# autopilot.net
KiCad netlist of a schematic drawn in EAGLE
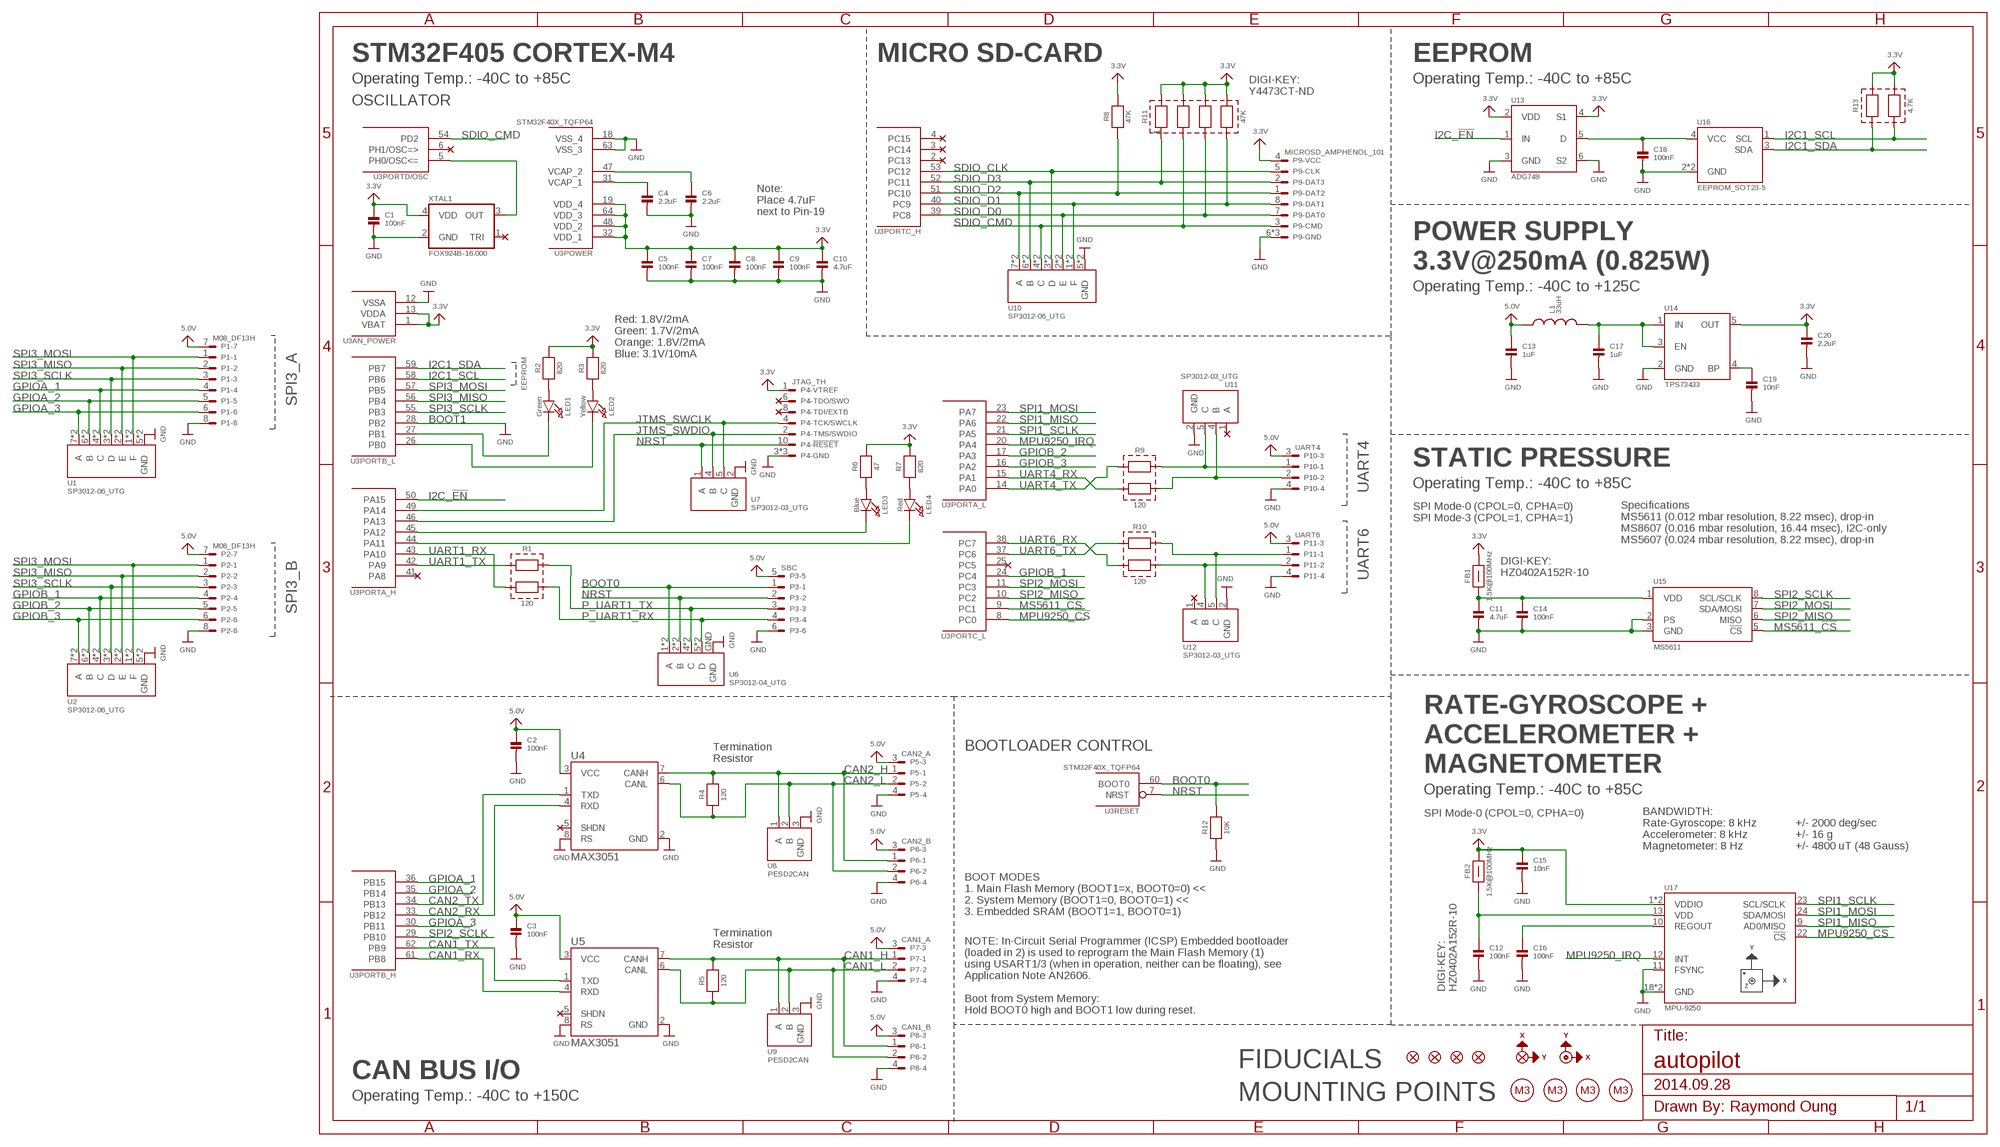
[diagram p0: schematic, sheet 1]

(export (version "E")
  (design (tool "Eeschema 10.0.6"))
  (components
    (comp (ref "AXIS3D1")
      (value "AXIS3D_DOWN")
      (footprint "eagle-import:AXIS3D_DOWN")
      (libsource (lib "eagle-import") (part "AXIS3D_DOWN"))
    )
    (comp (ref "AXIS3D2")
      (value "AXIS3D_UP")
      (footprint "eagle-import:AXIS3D_UP")
      (libsource (lib "eagle-import") (part "AXIS3D_UP"))
    )
    (comp (ref "C1")
      (value "100nF")
      (footprint "eagle-import:0402")
      (libsource (lib "eagle-import") (part "CAP_CERAMIC0402"))
    )
    (comp (ref "C2")
      (value "100nF")
      (footprint "eagle-import:0402")
      (libsource (lib "eagle-import") (part "CAP_CERAMIC0402"))
    )
    (comp (ref "C3")
      (value "100nF")
      (footprint "eagle-import:0402")
      (libsource (lib "eagle-import") (part "CAP_CERAMIC0402"))
    )
    (comp (ref "C4")
      (value "2.2uF")
      (footprint "eagle-import:0402")
      (libsource (lib "eagle-import") (part "CAP_CERAMIC0402"))
    )
    (comp (ref "C5")
      (value "100nF")
      (footprint "eagle-import:0402")
      (libsource (lib "eagle-import") (part "CAP_CERAMIC0402"))
    )
    (comp (ref "C6")
      (value "2.2uF")
      (footprint "eagle-import:0402")
      (libsource (lib "eagle-import") (part "CAP_CERAMIC0402"))
    )
    (comp (ref "C7")
      (value "100nF")
      (footprint "eagle-import:0402")
      (libsource (lib "eagle-import") (part "CAP_CERAMIC0402"))
    )
    (comp (ref "C8")
      (value "100nF")
      (footprint "eagle-import:0402")
      (libsource (lib "eagle-import") (part "CAP_CERAMIC0402"))
    )
    (comp (ref "C9")
      (value "100nF")
      (footprint "eagle-import:0402")
      (libsource (lib "eagle-import") (part "CAP_CERAMIC0402"))
    )
    (comp (ref "C10")
      (value "4.7uF")
      (footprint "eagle-import:0402")
      (libsource (lib "eagle-import") (part "CAP_CERAMIC0402"))
    )
    (comp (ref "C11")
      (value "4.7uF")
      (footprint "eagle-import:0402")
      (libsource (lib "eagle-import") (part "CAP_CERAMIC0402"))
    )
    (comp (ref "C12")
      (value "100nF")
      (footprint "eagle-import:0402")
      (libsource (lib "eagle-import") (part "CAP_CERAMIC0402"))
    )
    (comp (ref "C13")
      (value "1uF")
      (footprint "eagle-import:0402")
      (libsource (lib "eagle-import") (part "CAP_CERAMIC0402"))
    )
    (comp (ref "C14")
      (value "100nF")
      (footprint "eagle-import:0402")
      (libsource (lib "eagle-import") (part "CAP_CERAMIC0402"))
    )
    (comp (ref "C15")
      (value "10nF")
      (footprint "eagle-import:0402")
      (libsource (lib "eagle-import") (part "CAP_CERAMIC0402"))
    )
    (comp (ref "C16")
      (value "100nF")
      (footprint "eagle-import:0402")
      (libsource (lib "eagle-import") (part "CAP_CERAMIC0402"))
    )
    (comp (ref "C17")
      (value "1uF")
      (footprint "eagle-import:0402")
      (libsource (lib "eagle-import") (part "CAP_CERAMIC0402"))
    )
    (comp (ref "C18")
      (value "100nF")
      (footprint "eagle-import:0402")
      (libsource (lib "eagle-import") (part "CAP_CERAMIC0402"))
    )
    (comp (ref "C19")
      (value "10nF")
      (footprint "eagle-import:0402")
      (libsource (lib "eagle-import") (part "CAP_CERAMIC0402"))
    )
    (comp (ref "C20")
      (value "2.2uF")
      (footprint "eagle-import:0402")
      (libsource (lib "eagle-import") (part "CAP_CERAMIC0402"))
    )
    (comp (ref "FB1")
      (value "1.5K@100MHz")
      (footprint "eagle-import:0402")
      (libsource (lib "eagle-import") (part "FERRITE_0402"))
    )
    (comp (ref "FB2")
      (value "1.5K@100MHz")
      (footprint "eagle-import:0402")
      (libsource (lib "eagle-import") (part "FERRITE_0402"))
    )
    (comp (ref "L1")
      (value "33uH")
      (footprint "eagle-import:1210")
      (libsource (lib "eagle-import") (part "INDUCTOR_1210"))
    )
    (comp (ref "LED1")
      (value "Green")
      (footprint "eagle-import:CHIPLED_0603")
      (libsource (lib "eagle-import") (part "LED_0603"))
    )
    (comp (ref "LED2")
      (value "Yellow")
      (footprint "eagle-import:CHIPLED_0603")
      (libsource (lib "eagle-import") (part "LED_0603"))
    )
    (comp (ref "LED3")
      (value "Blue")
      (footprint "eagle-import:CHIPLED_0603")
      (libsource (lib "eagle-import") (part "LED_0603"))
    )
    (comp (ref "LED4")
      (value "Red")
      (footprint "eagle-import:CHIPLED_0603")
      (libsource (lib "eagle-import") (part "LED_0603"))
    )
    (comp (ref "MP1")
      (value "M3")
      (footprint "eagle-import:MP_M3")
      (libsource (lib "eagle-import") (part "M3"))
    )
    (comp (ref "MP2")
      (value "M3")
      (footprint "eagle-import:MP_M3")
      (libsource (lib "eagle-import") (part "M3"))
    )
    (comp (ref "MP3")
      (value "M3")
      (footprint "eagle-import:MP_M3")
      (libsource (lib "eagle-import") (part "M3"))
    )
    (comp (ref "MP4")
      (value "M3")
      (footprint "eagle-import:MP_M3")
      (libsource (lib "eagle-import") (part "M3"))
    )
    (comp (ref "P1")
      (value "M08_DF13H")
      (footprint "eagle-import:DF13A-8P-1.25H")
      (libsource (lib "eagle-import") (part "M08_DF13H"))
    )
    (comp (ref "P2")
      (value "M08_DF13H")
      (footprint "eagle-import:DF13A-8P-1.25H")
      (libsource (lib "eagle-import") (part "M08_DF13H"))
    )
    (comp (ref "P3")
      (value "SBC")
      (footprint "eagle-import:DF13A-6P-1.25H")
      (libsource (lib "eagle-import") (part "M06_DF13H"))
    )
    (comp (ref "P4")
      (value "JTAG_TH")
      (footprint "eagle-import:FTSH-105-01-XXX-DV")
      (libsource (lib "eagle-import") (part "JTAG_TH"))
    )
    (comp (ref "P5")
      (value "CAN2_A")
      (footprint "eagle-import:DF13A-4P-1.25H")
      (libsource (lib "eagle-import") (part "M04_DF13H"))
    )
    (comp (ref "P6")
      (value "CAN2_B")
      (footprint "eagle-import:DF13A-4P-1.25H")
      (libsource (lib "eagle-import") (part "M04_DF13H"))
    )
    (comp (ref "P7")
      (value "CAN1_A")
      (footprint "eagle-import:DF13A-4P-1.25H")
      (libsource (lib "eagle-import") (part "M04_DF13H"))
    )
    (comp (ref "P8")
      (value "CAN1_B")
      (footprint "eagle-import:DF13A-4P-1.25H")
      (libsource (lib "eagle-import") (part "M04_DF13H"))
    )
    (comp (ref "P9")
      (value "MICROSD_AMPHENOL_101")
      (footprint "eagle-import:AMPHENOL_101-00660-68")
      (libsource (lib "eagle-import") (part "MICROSD_AMPHENOL_101"))
    )
    (comp (ref "P10")
      (value "UART4")
      (footprint "eagle-import:DF13A-4P-1.25H")
      (libsource (lib "eagle-import") (part "M04_DF13H"))
    )
    (comp (ref "P11")
      (value "UART6")
      (footprint "eagle-import:DF13A-4P-1.25H")
      (libsource (lib "eagle-import") (part "M04_DF13H"))
    )
    (comp (ref "R1")
      (value "120")
      (footprint "eagle-import:EXBV4V")
      (libsource (lib "eagle-import") (part "RESISTOR2_0603X2"))
    )
    (comp (ref "R2")
      (value "820")
      (footprint "eagle-import:0402")
      (libsource (lib "eagle-import") (part "RESISTOR0402"))
    )
    (comp (ref "R3")
      (value "820")
      (footprint "eagle-import:0402")
      (libsource (lib "eagle-import") (part "RESISTOR0402"))
    )
    (comp (ref "R4")
      (value "120")
      (footprint "eagle-import:0603")
      (libsource (lib "eagle-import") (part "RESISTOR0603"))
    )
    (comp (ref "R5")
      (value "120")
      (footprint "eagle-import:0603")
      (libsource (lib "eagle-import") (part "RESISTOR0603"))
    )
    (comp (ref "R6")
      (value "47")
      (footprint "eagle-import:0402")
      (libsource (lib "eagle-import") (part "RESISTOR0402"))
    )
    (comp (ref "R7")
      (value "820")
      (footprint "eagle-import:0402")
      (libsource (lib "eagle-import") (part "RESISTOR0402"))
    )
    (comp (ref "R8")
      (value "47K")
      (footprint "eagle-import:0603")
      (libsource (lib "eagle-import") (part "RESISTOR0603"))
    )
    (comp (ref "R9")
      (value "120")
      (footprint "eagle-import:EXBV4V")
      (libsource (lib "eagle-import") (part "RESISTOR2_0603X2"))
    )
    (comp (ref "R10")
      (value "120")
      (footprint "eagle-import:EXBV4V")
      (libsource (lib "eagle-import") (part "RESISTOR2_0603X2"))
    )
    (comp (ref "R11")
      (value "47K")
      (footprint "eagle-import:EXBV8V")
      (libsource (lib "eagle-import") (part "RESISTOR4_0603X4"))
    )
    (comp (ref "R12")
      (value "10K")
      (footprint "eagle-import:0402")
      (libsource (lib "eagle-import") (part "RESISTOR0402"))
    )
    (comp (ref "R13")
      (value "4.7K")
      (footprint "eagle-import:EXBV4V")
      (libsource (lib "eagle-import") (part "RESISTOR2_0603X2"))
    )
    (comp (ref "REF1")
      (value "FIDUCIAL1X2.5")
      (footprint "eagle-import:POINT-1MM")
      (libsource (lib "eagle-import") (part "FIDUCIAL1X2.5"))
    )
    (comp (ref "REF2")
      (value "FIDUCIAL1X2.5")
      (footprint "eagle-import:POINT-1MM")
      (libsource (lib "eagle-import") (part "FIDUCIAL1X2.5"))
    )
    (comp (ref "REF3")
      (value "FIDUCIAL1X2.5")
      (footprint "eagle-import:POINT-1MM")
      (libsource (lib "eagle-import") (part "FIDUCIAL1X2.5"))
    )
    (comp (ref "REF4")
      (value "FIDUCIAL1X2.5")
      (footprint "eagle-import:POINT-1MM")
      (libsource (lib "eagle-import") (part "FIDUCIAL1X2.5"))
    )
    (comp (ref "U1")
      (value "SP3012-06_UTG")
      (footprint "eagle-import:UDFN14")
      (libsource (lib "eagle-import") (part "SP3012-06_UTG"))
    )
    (comp (ref "U2")
      (value "SP3012-06_UTG")
      (footprint "eagle-import:UDFN14")
      (libsource (lib "eagle-import") (part "SP3012-06_UTG"))
    )
    (comp (ref "U3")
      (value "STM32F40X_TQFP64")
      (footprint "eagle-import:TQFP64")
      (libsource (lib "eagle-import") (part "STM32F40X_TQFP64"))
    )
    (comp (ref "U4")
      (value "MAX3051")
      (footprint "eagle-import:SOT23-8")
      (libsource (lib "eagle-import") (part "MAX3051"))
    )
    (comp (ref "U5")
      (value "MAX3051")
      (footprint "eagle-import:SOT23-8")
      (libsource (lib "eagle-import") (part "MAX3051"))
    )
    (comp (ref "U6")
      (value "SP3012-04_UTG")
      (footprint "eagle-import:UDFN10")
      (libsource (lib "eagle-import") (part "SP3012-04_UTG"))
    )
    (comp (ref "U7")
      (value "SP3012-03_UTG")
      (footprint "eagle-import:UDFN06")
      (libsource (lib "eagle-import") (part "SP3012-03_UTG"))
    )
    (comp (ref "U8")
      (value "PESD2CAN")
      (footprint "eagle-import:SOT23-3")
      (libsource (lib "eagle-import") (part "PESD2CAN"))
    )
    (comp (ref "U9")
      (value "PESD2CAN")
      (footprint "eagle-import:SOT23-3")
      (libsource (lib "eagle-import") (part "PESD2CAN"))
    )
    (comp (ref "U10")
      (value "SP3012-06_UTG")
      (footprint "eagle-import:UDFN14")
      (libsource (lib "eagle-import") (part "SP3012-06_UTG"))
    )
    (comp (ref "U11")
      (value "SP3012-03_UTG")
      (footprint "eagle-import:UDFN06")
      (libsource (lib "eagle-import") (part "SP3012-03_UTG"))
    )
    (comp (ref "U12")
      (value "SP3012-03_UTG")
      (footprint "eagle-import:UDFN06")
      (libsource (lib "eagle-import") (part "SP3012-03_UTG"))
    )
    (comp (ref "U13")
      (value "ADG749")
      (footprint "eagle-import:SOT-363")
      (libsource (lib "eagle-import") (part "ADG749"))
    )
    (comp (ref "U14")
      (value "TPS73433")
      (footprint "eagle-import:SOT23-5")
      (libsource (lib "eagle-import") (part "TPS73433"))
    )
    (comp (ref "U15")
      (value "MS5611")
      (footprint "eagle-import:MS5611")
      (libsource (lib "eagle-import") (part "MS5611"))
    )
    (comp (ref "U16")
      (value "EEPROM_SOT23-5")
      (footprint "eagle-import:SOT23-5")
      (libsource (lib "eagle-import") (part "EEPROM_SOT23-5"))
    )
    (comp (ref "U17")
      (value "MPU-9250")
      (footprint "eagle-import:MPU-3X3")
      (libsource (lib "eagle-import") (part "MPU-9250"))
    )
    (comp (ref "XTAL1")
      (value "FOX924B-16.000")
      (footprint "eagle-import:OSCILLATOR-5.0X3.2A")
      (libsource (lib "eagle-import") (part "TCXO_5.0X3.2A"))
    )
  )
  (nets
    (net (code "1") (name "/BOOT0") (class "Default")
      (node (ref "P3") (pin "1") (pinfunction "S_1") (pintype "passive"))
      (node (ref "R12") (pin "2") (pinfunction "2_2") (pintype "passive"))
      (node (ref "U3") (pin "60") (pinfunction "BOOT0_60") (pintype "input"))
      (node (ref "U6") (pin "1") (pinfunction "A_1") (pintype "bidirectional"))
      (node (ref "U6") (pin "10") (pinfunction "A_10") (pintype "bidirectional"))
    )
    (net (code "2") (name "/CAN1_H") (class "Default")
      (node (ref "P7") (pin "1") (pinfunction "S_1") (pintype "passive"))
      (node (ref "P8") (pin "1") (pinfunction "S_1") (pintype "passive"))
      (node (ref "R5") (pin "2") (pinfunction "2_2") (pintype "passive"))
      (node (ref "U5") (pin "7") (pinfunction "CANH_7") (pintype "bidirectional"))
      (node (ref "U9") (pin "1") (pinfunction "A_1") (pintype "bidirectional"))
    )
    (net (code "3") (name "/CAN1_L") (class "Default")
      (node (ref "P7") (pin "2") (pinfunction "S_2") (pintype "passive"))
      (node (ref "P8") (pin "2") (pinfunction "S_2") (pintype "passive"))
      (node (ref "R5") (pin "1") (pinfunction "1_1") (pintype "passive"))
      (node (ref "U5") (pin "6") (pinfunction "CANL_6") (pintype "bidirectional"))
      (node (ref "U9") (pin "2") (pinfunction "B_2") (pintype "bidirectional"))
    )
    (net (code "4") (name "/CAN1_RX") (class "Default")
      (node (ref "U3") (pin "61") (pinfunction "PB8_61") (pintype "bidirectional"))
      (node (ref "U5") (pin "4") (pinfunction "RXD_4") (pintype "bidirectional"))
    )
    (net (code "5") (name "/CAN1_TX") (class "Default")
      (node (ref "U3") (pin "62") (pinfunction "PB9_62") (pintype "bidirectional"))
      (node (ref "U5") (pin "1") (pinfunction "TXD_1") (pintype "bidirectional"))
    )
    (net (code "6") (name "/CAN2_H") (class "Default")
      (node (ref "P5") (pin "1") (pinfunction "S_1") (pintype "passive"))
      (node (ref "P6") (pin "1") (pinfunction "S_1") (pintype "passive"))
      (node (ref "R4") (pin "2") (pinfunction "2_2") (pintype "passive"))
      (node (ref "U4") (pin "7") (pinfunction "CANH_7") (pintype "bidirectional"))
      (node (ref "U8") (pin "1") (pinfunction "A_1") (pintype "bidirectional"))
    )
    (net (code "7") (name "/CAN2_L") (class "Default")
      (node (ref "P5") (pin "2") (pinfunction "S_2") (pintype "passive"))
      (node (ref "P6") (pin "2") (pinfunction "S_2") (pintype "passive"))
      (node (ref "R4") (pin "1") (pinfunction "1_1") (pintype "passive"))
      (node (ref "U4") (pin "6") (pinfunction "CANL_6") (pintype "bidirectional"))
      (node (ref "U8") (pin "2") (pinfunction "B_2") (pintype "bidirectional"))
    )
    (net (code "8") (name "/CAN2_RX") (class "Default")
      (node (ref "U3") (pin "33") (pinfunction "PB12_33") (pintype "bidirectional"))
      (node (ref "U4") (pin "4") (pinfunction "RXD_4") (pintype "bidirectional"))
    )
    (net (code "9") (name "/CAN2_TX") (class "Default")
      (node (ref "U3") (pin "34") (pinfunction "PB13_34") (pintype "bidirectional"))
      (node (ref "U4") (pin "1") (pinfunction "TXD_1") (pintype "bidirectional"))
    )
    (net (code "10") (name "/GPIOA_1") (class "Default")
      (node (ref "P1") (pin "4") (pinfunction "S_4") (pintype "passive"))
      (node (ref "U1") (pin "11") (pinfunction "C_11") (pintype "passive"))
      (node (ref "U1") (pin "4") (pinfunction "C_4") (pintype "passive"))
      (node (ref "U3") (pin "36") (pinfunction "PB15_36") (pintype "bidirectional"))
    )
    (net (code "11") (name "/GPIOA_2") (class "Default")
      (node (ref "P1") (pin "5") (pinfunction "S_5") (pintype "passive"))
      (node (ref "U1") (pin "6") (pinfunction "B_6") (pintype "passive"))
      (node (ref "U1") (pin "9") (pinfunction "B_9") (pintype "passive"))
      (node (ref "U3") (pin "35") (pinfunction "PB14_35") (pintype "bidirectional"))
    )
    (net (code "12") (name "/GPIOA_3") (class "Default")
      (node (ref "P1") (pin "6") (pinfunction "S_6") (pintype "passive"))
      (node (ref "U1") (pin "7") (pinfunction "A_7") (pintype "passive"))
      (node (ref "U1") (pin "8") (pinfunction "A_8") (pintype "passive"))
      (node (ref "U3") (pin "30") (pinfunction "PB11_30") (pintype "bidirectional"))
    )
    (net (code "13") (name "/GPIOB_1") (class "Default")
      (node (ref "P2") (pin "4") (pinfunction "S_4") (pintype "passive"))
      (node (ref "U2") (pin "11") (pinfunction "C_11") (pintype "passive"))
      (node (ref "U2") (pin "4") (pinfunction "C_4") (pintype "passive"))
      (node (ref "U3") (pin "24") (pinfunction "PC4_24") (pintype "bidirectional"))
    )
    (net (code "14") (name "/GPIOB_2") (class "Default")
      (node (ref "P2") (pin "5") (pinfunction "S_5") (pintype "passive"))
      (node (ref "U2") (pin "6") (pinfunction "B_6") (pintype "passive"))
      (node (ref "U2") (pin "9") (pinfunction "B_9") (pintype "passive"))
      (node (ref "U3") (pin "17") (pinfunction "PA3_17") (pintype "bidirectional"))
    )
    (net (code "15") (name "/GPIOB_3") (class "Default")
      (node (ref "P2") (pin "6") (pinfunction "S_6") (pintype "passive"))
      (node (ref "U2") (pin "7") (pinfunction "A_7") (pintype "passive"))
      (node (ref "U2") (pin "8") (pinfunction "A_8") (pintype "passive"))
      (node (ref "U3") (pin "16") (pinfunction "PA2_16") (pintype "bidirectional"))
    )
    (net (code "16") (name "/I2C1_SCL") (class "Default")
      (node (ref "R13") (pin "2") (pinfunction "2_2") (pintype "passive"))
      (node (ref "U16") (pin "1") (pinfunction "SCL_1") (pintype "bidirectional"))
      (node (ref "U3") (pin "58") (pinfunction "PB6_58") (pintype "bidirectional"))
    )
    (net (code "17") (name "/I2C1_SDA") (class "Default")
      (node (ref "R13") (pin "1") (pinfunction "1_1") (pintype "passive"))
      (node (ref "U16") (pin "3") (pinfunction "SDA_3") (pintype "bidirectional"))
      (node (ref "U3") (pin "59") (pinfunction "PB7_59") (pintype "bidirectional"))
    )
    (net (code "18") (name "/I2C_~{EN}") (class "Default")
      (node (ref "U13") (pin "1") (pinfunction "IN_1") (pintype "bidirectional"))
      (node (ref "U3") (pin "50") (pinfunction "PA15_50") (pintype "bidirectional"))
    )
    (net (code "19") (name "/JTMS_SWCLK") (class "Default")
      (node (ref "P4") (pin "4") (pinfunction "S_4") (pintype "passive"))
      (node (ref "U3") (pin "49") (pinfunction "PA14_49") (pintype "bidirectional"))
      (node (ref "U7") (pin "5") (pinfunction "C_5") (pintype "bidirectional"))
    )
    (net (code "20") (name "/JTMS_SWDIO") (class "Default")
      (node (ref "P4") (pin "2") (pinfunction "S_2") (pintype "passive"))
      (node (ref "U3") (pin "46") (pinfunction "PA13_46") (pintype "bidirectional"))
      (node (ref "U7") (pin "4") (pinfunction "B_4") (pintype "bidirectional"))
    )
    (net (code "21") (name "/MPU9250_IRQ") (class "Default")
      (node (ref "U17") (pin "12") (pinfunction "INT_12") (pintype "bidirectional"))
      (node (ref "U3") (pin "20") (pinfunction "PA4_20") (pintype "bidirectional"))
    )
    (net (code "22") (name "/MPU9250_~{CS}") (class "Default")
      (node (ref "U17") (pin "22") (pinfunction "~{CS}_22") (pintype "bidirectional"))
      (node (ref "U3") (pin "8") (pinfunction "PC0_8") (pintype "bidirectional"))
    )
    (net (code "23") (name "/MS5611_~{CS}") (class "Default")
      (node (ref "U15") (pin "5") (pinfunction "~{CS}_5") (pintype "bidirectional"))
      (node (ref "U3") (pin "9") (pinfunction "PC1_9") (pintype "bidirectional"))
    )
    (net (code "24") (name "/NRST") (class "Default")
      (node (ref "P3") (pin "2") (pinfunction "S_2") (pintype "passive"))
      (node (ref "P4") (pin "10") (pinfunction "S_10") (pintype "passive"))
      (node (ref "U3") (pin "7") (pinfunction "NRST_7") (pintype "input"))
      (node (ref "U6") (pin "2") (pinfunction "B_2") (pintype "bidirectional"))
      (node (ref "U6") (pin "9") (pinfunction "B_9") (pintype "bidirectional"))
      (node (ref "U7") (pin "1") (pinfunction "A_1") (pintype "bidirectional"))
    )
    (net (code "25") (name "/P_UART1_RX") (class "Default")
      (node (ref "P3") (pin "4") (pinfunction "S_4") (pintype "passive"))
      (node (ref "R1") (pin "3") (pinfunction "3_3") (pintype "passive"))
      (node (ref "U6") (pin "5") (pinfunction "D_5") (pintype "bidirectional"))
      (node (ref "U6") (pin "6") (pinfunction "D_6") (pintype "bidirectional"))
    )
    (net (code "26") (name "/P_UART1_TX") (class "Default")
      (node (ref "P3") (pin "3") (pinfunction "S_3") (pintype "passive"))
      (node (ref "R1") (pin "4") (pinfunction "4_4") (pintype "passive"))
      (node (ref "U6") (pin "4") (pinfunction "C_4") (pintype "bidirectional"))
      (node (ref "U6") (pin "7") (pinfunction "C_7") (pintype "bidirectional"))
    )
    (net (code "27") (name "/SDIO_CLK") (class "Default")
      (node (ref "P9") (pin "5") (pinfunction "S_5") (pintype "passive"))
      (node (ref "U10") (pin "12") (pinfunction "D_12") (pintype "passive"))
      (node (ref "U10") (pin "3") (pinfunction "D_3") (pintype "passive"))
      (node (ref "U3") (pin "53") (pinfunction "PC12_53") (pintype "bidirectional"))
    )
    (net (code "28") (name "/SDIO_CMD") (class "Default")
      (node (ref "P9") (pin "3") (pinfunction "S_3") (pintype "passive"))
      (node (ref "R11") (pin "2") (pinfunction "2_2") (pintype "passive"))
      (node (ref "U10") (pin "11") (pinfunction "C_11") (pintype "passive"))
      (node (ref "U10") (pin "4") (pinfunction "C_4") (pintype "passive"))
      (node (ref "U3") (pin "54") (pinfunction "PD2_54") (pintype "bidirectional"))
    )
    (net (code "29") (name "/SDIO_D0") (class "Default")
      (node (ref "P9") (pin "7") (pinfunction "S_7") (pintype "passive"))
      (node (ref "R11") (pin "3") (pinfunction "3_3") (pintype "passive"))
      (node (ref "U10") (pin "13") (pinfunction "E_13") (pintype "passive"))
      (node (ref "U10") (pin "2") (pinfunction "E_2") (pintype "passive"))
      (node (ref "U3") (pin "39") (pinfunction "PC8_39") (pintype "bidirectional"))
    )
    (net (code "30") (name "/SDIO_D1") (class "Default")
      (node (ref "P9") (pin "8") (pinfunction "S_8") (pintype "passive"))
      (node (ref "R11") (pin "4") (pinfunction "4_4") (pintype "passive"))
      (node (ref "U10") (pin "1") (pinfunction "F_1") (pintype "passive"))
      (node (ref "U10") (pin "14") (pinfunction "F_14") (pintype "passive"))
      (node (ref "U3") (pin "40") (pinfunction "PC9_40") (pintype "bidirectional"))
    )
    (net (code "31") (name "/SDIO_D2") (class "Default")
      (node (ref "P9") (pin "1") (pinfunction "S_1") (pintype "passive"))
      (node (ref "R8") (pin "1") (pinfunction "1_1") (pintype "passive"))
      (node (ref "U10") (pin "7") (pinfunction "A_7") (pintype "passive"))
      (node (ref "U10") (pin "8") (pinfunction "A_8") (pintype "passive"))
      (node (ref "U3") (pin "51") (pinfunction "PC10_51") (pintype "bidirectional"))
    )
    (net (code "32") (name "/SDIO_D3") (class "Default")
      (node (ref "P9") (pin "2") (pinfunction "S_2") (pintype "passive"))
      (node (ref "R11") (pin "1") (pinfunction "1_1") (pintype "passive"))
      (node (ref "U10") (pin "6") (pinfunction "B_6") (pintype "passive"))
      (node (ref "U10") (pin "9") (pinfunction "B_9") (pintype "passive"))
      (node (ref "U3") (pin "52") (pinfunction "PC11_52") (pintype "bidirectional"))
    )
    (net (code "33") (name "/SPI1_MISO") (class "Default")
      (node (ref "U17") (pin "9") (pinfunction "AD0/MISO_9") (pintype "bidirectional"))
      (node (ref "U3") (pin "22") (pinfunction "PA6_22") (pintype "bidirectional"))
    )
    (net (code "34") (name "/SPI1_MOSI") (class "Default")
      (node (ref "U17") (pin "24") (pinfunction "SDA/MOSI_24") (pintype "bidirectional"))
      (node (ref "U3") (pin "23") (pinfunction "PA7_23") (pintype "bidirectional"))
    )
    (net (code "35") (name "/SPI1_SCLK") (class "Default")
      (node (ref "U17") (pin "23") (pinfunction "SCL/SCLK_23") (pintype "bidirectional"))
      (node (ref "U3") (pin "21") (pinfunction "PA5_21") (pintype "bidirectional"))
    )
    (net (code "36") (name "/SPI2_MISO") (class "Default")
      (node (ref "U15") (pin "6") (pinfunction "MISO_6") (pintype "bidirectional"))
      (node (ref "U3") (pin "10") (pinfunction "PC2_10") (pintype "bidirectional"))
    )
    (net (code "37") (name "/SPI2_MOSI") (class "Default")
      (node (ref "U15") (pin "7") (pinfunction "SDA/MOSI_7") (pintype "bidirectional"))
      (node (ref "U3") (pin "11") (pinfunction "PC3_11") (pintype "bidirectional"))
    )
    (net (code "38") (name "/SPI2_SCLK") (class "Default")
      (node (ref "U15") (pin "8") (pinfunction "SCL/SCLK_8") (pintype "bidirectional"))
      (node (ref "U3") (pin "29") (pinfunction "PB10_29") (pintype "bidirectional"))
    )
    (net (code "39") (name "/SPI3_MISO") (class "Default")
      (node (ref "P1") (pin "2") (pinfunction "S_2") (pintype "passive"))
      (node (ref "P2") (pin "2") (pinfunction "S_2") (pintype "passive"))
      (node (ref "U1") (pin "13") (pinfunction "E_13") (pintype "passive"))
      (node (ref "U1") (pin "2") (pinfunction "E_2") (pintype "passive"))
      (node (ref "U2") (pin "13") (pinfunction "E_13") (pintype "passive"))
      (node (ref "U2") (pin "2") (pinfunction "E_2") (pintype "passive"))
      (node (ref "U3") (pin "56") (pinfunction "PB4_56") (pintype "bidirectional"))
    )
    (net (code "40") (name "/SPI3_MOSI") (class "Default")
      (node (ref "P1") (pin "1") (pinfunction "S_1") (pintype "passive"))
      (node (ref "P2") (pin "1") (pinfunction "S_1") (pintype "passive"))
      (node (ref "U1") (pin "1") (pinfunction "F_1") (pintype "passive"))
      (node (ref "U1") (pin "14") (pinfunction "F_14") (pintype "passive"))
      (node (ref "U2") (pin "1") (pinfunction "F_1") (pintype "passive"))
      (node (ref "U2") (pin "14") (pinfunction "F_14") (pintype "passive"))
      (node (ref "U3") (pin "57") (pinfunction "PB5_57") (pintype "bidirectional"))
    )
    (net (code "41") (name "/SPI3_SCLK") (class "Default")
      (node (ref "P1") (pin "3") (pinfunction "S_3") (pintype "passive"))
      (node (ref "P2") (pin "3") (pinfunction "S_3") (pintype "passive"))
      (node (ref "U1") (pin "12") (pinfunction "D_12") (pintype "passive"))
      (node (ref "U1") (pin "3") (pinfunction "D_3") (pintype "passive"))
      (node (ref "U2") (pin "12") (pinfunction "D_12") (pintype "passive"))
      (node (ref "U2") (pin "3") (pinfunction "D_3") (pintype "passive"))
      (node (ref "U3") (pin "55") (pinfunction "PB3_55") (pintype "bidirectional"))
    )
    (net (code "42") (name "/UART1_RX") (class "Default")
      (node (ref "R1") (pin "2") (pinfunction "2_2") (pintype "passive"))
      (node (ref "U3") (pin "43") (pinfunction "PA10_43") (pintype "bidirectional"))
    )
    (net (code "43") (name "/UART1_TX") (class "Default")
      (node (ref "R1") (pin "1") (pinfunction "1_1") (pintype "passive"))
      (node (ref "U3") (pin "42") (pinfunction "PA9_42") (pintype "bidirectional"))
    )
    (net (code "44") (name "/UART4_RX") (class "Default")
      (node (ref "R9") (pin "2") (pinfunction "2_2") (pintype "passive"))
      (node (ref "U3") (pin "15") (pinfunction "PA1_15") (pintype "bidirectional"))
    )
    (net (code "45") (name "/UART4_TX") (class "Default")
      (node (ref "R9") (pin "1") (pinfunction "1_1") (pintype "passive"))
      (node (ref "U3") (pin "14") (pinfunction "PA0_14") (pintype "bidirectional"))
    )
    (net (code "46") (name "/UART6_RX") (class "Default")
      (node (ref "R10") (pin "2") (pinfunction "2_2") (pintype "passive"))
      (node (ref "U3") (pin "38") (pinfunction "PC7_38") (pintype "bidirectional"))
    )
    (net (code "47") (name "/UART6_TX") (class "Default")
      (node (ref "R10") (pin "1") (pinfunction "1_1") (pintype "passive"))
      (node (ref "U3") (pin "37") (pinfunction "PC6_37") (pintype "bidirectional"))
    )
    (net (code "48") (name "3.3V") (class "Default")
      (node (ref "C1") (pin "1") (pinfunction "P$1_1") (pintype "passive"))
      (node (ref "C10") (pin "1") (pinfunction "P$1_1") (pintype "passive"))
      (node (ref "C15") (pin "1") (pinfunction "P$1_1") (pintype "passive"))
      (node (ref "C20") (pin "1") (pinfunction "P$1_1") (pintype "passive"))
      (node (ref "C5") (pin "1") (pinfunction "P$1_1") (pintype "passive"))
      (node (ref "C7") (pin "1") (pinfunction "P$1_1") (pintype "passive"))
      (node (ref "C8") (pin "1") (pinfunction "P$1_1") (pintype "passive"))
      (node (ref "C9") (pin "1") (pinfunction "P$1_1") (pintype "passive"))
      (node (ref "FB1") (pin "2") (pinfunction "2_2") (pintype "passive"))
      (node (ref "FB2") (pin "2") (pinfunction "2_2") (pintype "passive"))
      (node (ref "P4") (pin "1") (pinfunction "S_1") (pintype "passive"))
      (node (ref "P9") (pin "4") (pinfunction "S_4") (pintype "passive"))
      (node (ref "R11") (pin "5") (pinfunction "5_5") (pintype "passive"))
      (node (ref "R11") (pin "6") (pinfunction "6_6") (pintype "passive"))
      (node (ref "R11") (pin "7") (pinfunction "7_7") (pintype "passive"))
      (node (ref "R11") (pin "8") (pinfunction "8_8") (pintype "passive"))
      (node (ref "R13") (pin "3") (pinfunction "3_3") (pintype "passive"))
      (node (ref "R13") (pin "4") (pinfunction "4_4") (pintype "passive"))
      (node (ref "R2") (pin "2") (pinfunction "2_2") (pintype "passive"))
      (node (ref "R3") (pin "2") (pinfunction "2_2") (pintype "passive"))
      (node (ref "R6") (pin "2") (pinfunction "2_2") (pintype "passive"))
      (node (ref "R7") (pin "2") (pinfunction "2_2") (pintype "passive"))
      (node (ref "R8") (pin "2") (pinfunction "2_2") (pintype "passive"))
      (node (ref "U13") (pin "2") (pinfunction "VDD_2") (pintype "bidirectional"))
      (node (ref "U13") (pin "4") (pinfunction "S1_4") (pintype "bidirectional"))
      (node (ref "U14") (pin "5") (pinfunction "OUT_5") (pintype "bidirectional"))
      (node (ref "U17") (pin "1") (pinfunction "VDDIO_1") (pintype "bidirectional"))
      (node (ref "U17") (pin "8") (pinfunction "VDDIO_8") (pintype "bidirectional"))
      (node (ref "U3") (pin "1") (pinfunction "VBAT_1") (pintype "power_in"))
      (node (ref "U3") (pin "13") (pinfunction "VDDA_13") (pintype "power_in"))
      (node (ref "U3") (pin "19") (pinfunction "VDD_4_19") (pintype "power_in"))
      (node (ref "U3") (pin "32") (pinfunction "VDD_1_32") (pintype "power_in"))
      (node (ref "U3") (pin "48") (pinfunction "VDD_2_48") (pintype "power_in"))
      (node (ref "U3") (pin "64") (pinfunction "VDD_3_64") (pintype "power_in"))
      (node (ref "XTAL1") (pin "4") (pinfunction "VDD_4") (pintype "bidirectional"))
    )
    (net (code "49") (name "5.0V") (class "Default")
      (node (ref "C13") (pin "1") (pinfunction "P$1_1") (pintype "passive"))
      (node (ref "C2") (pin "1") (pinfunction "P$1_1") (pintype "passive"))
      (node (ref "C3") (pin "1") (pinfunction "P$1_1") (pintype "passive"))
      (node (ref "L1") (pin "1") (pinfunction "1_1") (pintype "passive"))
      (node (ref "P1") (pin "7") (pinfunction "S_7") (pintype "passive"))
      (node (ref "P10") (pin "3") (pinfunction "S_3") (pintype "passive"))
      (node (ref "P11") (pin "3") (pinfunction "S_3") (pintype "passive"))
      (node (ref "P2") (pin "7") (pinfunction "S_7") (pintype "passive"))
      (node (ref "P3") (pin "5") (pinfunction "S_5") (pintype "passive"))
      (node (ref "P5") (pin "3") (pinfunction "S_3") (pintype "passive"))
      (node (ref "P6") (pin "3") (pinfunction "S_3") (pintype "passive"))
      (node (ref "P7") (pin "3") (pinfunction "S_3") (pintype "passive"))
      (node (ref "P8") (pin "3") (pinfunction "S_3") (pintype "passive"))
      (node (ref "U4") (pin "3") (pinfunction "VCC_3") (pintype "bidirectional"))
      (node (ref "U5") (pin "3") (pinfunction "VCC_3") (pintype "bidirectional"))
    )
    (net (code "50") (name "GND") (class "Default")
      (node (ref "C1") (pin "2") (pinfunction "P$2_2") (pintype "passive"))
      (node (ref "C10") (pin "2") (pinfunction "P$2_2") (pintype "passive"))
      (node (ref "C11") (pin "2") (pinfunction "P$2_2") (pintype "passive"))
      (node (ref "C12") (pin "2") (pinfunction "P$2_2") (pintype "passive"))
      (node (ref "C13") (pin "2") (pinfunction "P$2_2") (pintype "passive"))
      (node (ref "C14") (pin "2") (pinfunction "P$2_2") (pintype "passive"))
      (node (ref "C15") (pin "2") (pinfunction "P$2_2") (pintype "passive"))
      (node (ref "C16") (pin "2") (pinfunction "P$2_2") (pintype "passive"))
      (node (ref "C17") (pin "2") (pinfunction "P$2_2") (pintype "passive"))
      (node (ref "C18") (pin "2") (pinfunction "P$2_2") (pintype "passive"))
      (node (ref "C19") (pin "2") (pinfunction "P$2_2") (pintype "passive"))
      (node (ref "C2") (pin "2") (pinfunction "P$2_2") (pintype "passive"))
      (node (ref "C20") (pin "2") (pinfunction "P$2_2") (pintype "passive"))
      (node (ref "C3") (pin "2") (pinfunction "P$2_2") (pintype "passive"))
      (node (ref "C4") (pin "2") (pinfunction "P$2_2") (pintype "passive"))
      (node (ref "C5") (pin "2") (pinfunction "P$2_2") (pintype "passive"))
      (node (ref "C6") (pin "2") (pinfunction "P$2_2") (pintype "passive"))
      (node (ref "C7") (pin "2") (pinfunction "P$2_2") (pintype "passive"))
      (node (ref "C8") (pin "2") (pinfunction "P$2_2") (pintype "passive"))
      (node (ref "C9") (pin "2") (pinfunction "P$2_2") (pintype "passive"))
      (node (ref "P1") (pin "8") (pinfunction "S_8") (pintype "passive"))
      (node (ref "P10") (pin "4") (pinfunction "S_4") (pintype "passive"))
      (node (ref "P11") (pin "4") (pinfunction "S_4") (pintype "passive"))
      (node (ref "P2") (pin "8") (pinfunction "S_8") (pintype "passive"))
      (node (ref "P3") (pin "6") (pinfunction "S_6") (pintype "passive"))
      (node (ref "P4") (pin "3") (pinfunction "S_3") (pintype "passive"))
      (node (ref "P4") (pin "5") (pinfunction "S_5") (pintype "passive"))
      (node (ref "P4") (pin "9") (pinfunction "S_9") (pintype "passive"))
      (node (ref "P5") (pin "4") (pinfunction "S_4") (pintype "passive"))
      (node (ref "P6") (pin "4") (pinfunction "S_4") (pintype "passive"))
      (node (ref "P7") (pin "4") (pinfunction "S_4") (pintype "passive"))
      (node (ref "P8") (pin "4") (pinfunction "S_4") (pintype "passive"))
      (node (ref "P9") (pin "6") (pinfunction "S_6") (pintype "passive"))
      (node (ref "P9") (pin "GND1") (pinfunction "S_GND1") (pintype "passive"))
      (node (ref "P9") (pin "GND3") (pinfunction "S_GND3") (pintype "passive"))
      (node (ref "R12") (pin "1") (pinfunction "1_1") (pintype "passive"))
      (node (ref "U1") (pin "10") (pinfunction "GND_10") (pintype "power_in"))
      (node (ref "U1") (pin "5") (pinfunction "GND_5") (pintype "power_in"))
      (node (ref "U10") (pin "10") (pinfunction "GND_10") (pintype "power_in"))
      (node (ref "U10") (pin "5") (pinfunction "GND_5") (pintype "power_in"))
      (node (ref "U11") (pin "2") (pinfunction "GND_2") (pintype "power_in"))
      (node (ref "U12") (pin "2") (pinfunction "GND_2") (pintype "power_in"))
      (node (ref "U13") (pin "3") (pinfunction "GND_3") (pintype "bidirectional"))
      (node (ref "U13") (pin "6") (pinfunction "S2_6") (pintype "bidirectional"))
      (node (ref "U14") (pin "2") (pinfunction "GND_2") (pintype "bidirectional"))
      (node (ref "U15") (pin "2") (pinfunction "PS_2") (pintype "passive"))
      (node (ref "U15") (pin "3") (pinfunction "GND_3") (pintype "power_in"))
      (node (ref "U16") (pin "2") (pinfunction "GND_2") (pintype "bidirectional"))
      (node (ref "U16") (pin "5") (pinfunction "GND_5") (pintype "bidirectional"))
      (node (ref "U17") (pin "11") (pinfunction "FSYNC_11") (pintype "bidirectional"))
      (node (ref "U17") (pin "18") (pinfunction "GND_18") (pintype "bidirectional"))
      (node (ref "U17") (pin "20") (pinfunction "GND_20") (pintype "bidirectional"))
      (node (ref "U2") (pin "10") (pinfunction "GND_10") (pintype "power_in"))
      (node (ref "U2") (pin "5") (pinfunction "GND_5") (pintype "power_in"))
      (node (ref "U3") (pin "12") (pinfunction "VSSA_12") (pintype "power_in"))
      (node (ref "U3") (pin "18") (pinfunction "VSS_4_18") (pintype "power_in"))
      (node (ref "U3") (pin "28") (pinfunction "PB2_28") (pintype "bidirectional"))
      (node (ref "U3") (pin "63") (pinfunction "VSS_3_63") (pintype "power_in"))
      (node (ref "U4") (pin "2") (pinfunction "GND_2") (pintype "bidirectional"))
      (node (ref "U4") (pin "8") (pinfunction "RS_8") (pintype "bidirectional"))
      (node (ref "U5") (pin "2") (pinfunction "GND_2") (pintype "bidirectional"))
      (node (ref "U5") (pin "8") (pinfunction "RS_8") (pintype "bidirectional"))
      (node (ref "U6") (pin "GND") (pinfunction "GND_GND") (pintype "power_in"))
      (node (ref "U7") (pin "2") (pinfunction "GND_2") (pintype "power_in"))
      (node (ref "U8") (pin "3") (pinfunction "GND_3") (pintype "power_in"))
      (node (ref "U9") (pin "3") (pinfunction "GND_3") (pintype "power_in"))
      (node (ref "XTAL1") (pin "2") (pinfunction "GND_2") (pintype "bidirectional"))
    )
    (net (code "51") (name "Net-(C4-P$1)") (class "Default")
      (node (ref "C4") (pin "1") (pinfunction "P$1_1") (pintype "passive"))
      (node (ref "U3") (pin "31") (pinfunction "VCAP_1_31") (pintype "power_in"))
    )
    (net (code "52") (name "Net-(C6-P$1)") (class "Default")
      (node (ref "C6") (pin "1") (pinfunction "P$1_1") (pintype "passive"))
      (node (ref "U3") (pin "47") (pinfunction "VCAP_2_47") (pintype "power_in"))
    )
    (net (code "53") (name "Net-(C11-P$1)") (class "Default")
      (node (ref "C11") (pin "1") (pinfunction "P$1_1") (pintype "passive"))
      (node (ref "C14") (pin "1") (pinfunction "P$1_1") (pintype "passive"))
      (node (ref "FB1") (pin "1") (pinfunction "1_1") (pintype "passive"))
      (node (ref "U15") (pin "1") (pinfunction "VDD_1") (pintype "power_in"))
    )
    (net (code "54") (name "Net-(C12-P$1)") (class "Default")
      (node (ref "C12") (pin "1") (pinfunction "P$1_1") (pintype "passive"))
      (node (ref "FB2") (pin "1") (pinfunction "1_1") (pintype "passive"))
      (node (ref "U17") (pin "13") (pinfunction "VDD_13") (pintype "bidirectional"))
    )
    (net (code "55") (name "Net-(C16-P$1)") (class "Default")
      (node (ref "C16") (pin "1") (pinfunction "P$1_1") (pintype "passive"))
      (node (ref "U17") (pin "10") (pinfunction "REGOUT_10") (pintype "bidirectional"))
    )
    (net (code "56") (name "Net-(C17-P$1)") (class "Default")
      (node (ref "C17") (pin "1") (pinfunction "P$1_1") (pintype "passive"))
      (node (ref "L1") (pin "2") (pinfunction "2_2") (pintype "passive"))
      (node (ref "U14") (pin "1") (pinfunction "IN_1") (pintype "bidirectional"))
      (node (ref "U14") (pin "3") (pinfunction "EN_3") (pintype "bidirectional"))
    )
    (net (code "57") (name "Net-(C18-P$1)") (class "Default")
      (node (ref "C18") (pin "1") (pinfunction "P$1_1") (pintype "passive"))
      (node (ref "U13") (pin "5") (pinfunction "D_5") (pintype "bidirectional"))
      (node (ref "U16") (pin "4") (pinfunction "VCC_4") (pintype "bidirectional"))
    )
    (net (code "58") (name "Net-(C19-P$1)") (class "Default")
      (node (ref "C19") (pin "1") (pinfunction "P$1_1") (pintype "passive"))
      (node (ref "U14") (pin "4") (pinfunction "BP_4") (pintype "bidirectional"))
    )
    (net (code "59") (name "Net-(LED1-PadA)") (class "Default")
      (node (ref "LED1") (pin "A") (pinfunction "A_A") (pintype "passive"))
      (node (ref "R2") (pin "1") (pinfunction "1_1") (pintype "passive"))
    )
    (net (code "60") (name "Net-(LED2-PadA)") (class "Default")
      (node (ref "LED2") (pin "A") (pinfunction "A_A") (pintype "passive"))
      (node (ref "R3") (pin "1") (pinfunction "1_1") (pintype "passive"))
    )
    (net (code "61") (name "Net-(LED3-PadA)") (class "Default")
      (node (ref "LED3") (pin "A") (pinfunction "A_A") (pintype "passive"))
      (node (ref "R6") (pin "1") (pinfunction "1_1") (pintype "passive"))
    )
    (net (code "62") (name "Net-(LED4-PadA)") (class "Default")
      (node (ref "LED4") (pin "A") (pinfunction "A_A") (pintype "passive"))
      (node (ref "R7") (pin "1") (pinfunction "1_1") (pintype "passive"))
    )
    (net (code "63") (name "Net-(P10A-S)") (class "Default")
      (node (ref "P10") (pin "1") (pinfunction "S_1") (pintype "passive"))
      (node (ref "R9") (pin "4") (pinfunction "4_4") (pintype "passive"))
      (node (ref "U11") (pin "5") (pinfunction "C_5") (pintype "bidirectional"))
    )
    (net (code "64") (name "Net-(P10B-S)") (class "Default")
      (node (ref "P10") (pin "2") (pinfunction "S_2") (pintype "passive"))
      (node (ref "R9") (pin "3") (pinfunction "3_3") (pintype "passive"))
      (node (ref "U11") (pin "4") (pinfunction "B_4") (pintype "bidirectional"))
    )
    (net (code "65") (name "Net-(P11A-S)") (class "Default")
      (node (ref "P11") (pin "1") (pinfunction "S_1") (pintype "passive"))
      (node (ref "R10") (pin "4") (pinfunction "4_4") (pintype "passive"))
      (node (ref "U12") (pin "5") (pinfunction "C_5") (pintype "bidirectional"))
    )
    (net (code "66") (name "Net-(P11B-S)") (class "Default")
      (node (ref "P11") (pin "2") (pinfunction "S_2") (pintype "passive"))
      (node (ref "R10") (pin "3") (pinfunction "3_3") (pintype "passive"))
      (node (ref "U12") (pin "4") (pinfunction "B_4") (pintype "bidirectional"))
    )
    (net (code "67") (name "Net-(U3B-PA11)") (class "Default")
      (node (ref "LED4") (pin "C") (pinfunction "C_C") (pintype "passive"))
      (node (ref "U3") (pin "44") (pinfunction "PA11_44") (pintype "bidirectional"))
    )
    (net (code "68") (name "Net-(U3B-PA12)") (class "Default")
      (node (ref "LED3") (pin "C") (pinfunction "C_C") (pintype "passive"))
      (node (ref "U3") (pin "45") (pinfunction "PA12_45") (pintype "bidirectional"))
    )
    (net (code "69") (name "Net-(U3E-PB0)") (class "Default")
      (node (ref "LED2") (pin "C") (pinfunction "C_C") (pintype "passive"))
      (node (ref "U3") (pin "26") (pinfunction "PB0_26") (pintype "bidirectional"))
    )
    (net (code "70") (name "Net-(U3E-PB1)") (class "Default")
      (node (ref "LED1") (pin "C") (pinfunction "C_C") (pintype "passive"))
      (node (ref "U3") (pin "27") (pinfunction "PB1_27") (pintype "bidirectional"))
    )
    (net (code "71") (name "Net-(U3H-PH0{slash}OSC<=)") (class "Default")
      (node (ref "U3") (pin "5") (pinfunction "PH0/OSC<=_5") (pintype "bidirectional"))
      (node (ref "XTAL1") (pin "3") (pinfunction "OUT_3") (pintype "bidirectional"))
    )
    (net (code "72") (name "unconnected-(P4D-S-Pad8)") (class "Default")
      (node (ref "P4") (pin "8") (pinfunction "S_8") (pintype "passive"))
    )
    (net (code "73") (name "unconnected-(P4E-S-Pad6)") (class "Default")
      (node (ref "P4") (pin "6") (pinfunction "S_6") (pintype "passive"))
    )
    (net (code "74") (name "unconnected-(U3B-PA8-Pad41)") (class "Default")
      (node (ref "U3") (pin "41") (pinfunction "PA8_41") (pintype "bidirectional"))
    )
    (net (code "75") (name "unconnected-(U3F-PC13-Pad2)") (class "Default")
      (node (ref "U3") (pin "2") (pinfunction "PC13_2") (pintype "bidirectional"))
    )
    (net (code "76") (name "unconnected-(U3F-PC14-Pad3)") (class "Default")
      (node (ref "U3") (pin "3") (pinfunction "PC14_3") (pintype "bidirectional"))
    )
    (net (code "77") (name "unconnected-(U3F-PC15-Pad4)") (class "Default")
      (node (ref "U3") (pin "4") (pinfunction "PC15_4") (pintype "bidirectional"))
    )
    (net (code "78") (name "unconnected-(U3G-PC5-Pad25)") (class "Default")
      (node (ref "U3") (pin "25") (pinfunction "PC5_25") (pintype "bidirectional"))
    )
    (net (code "79") (name "unconnected-(U3H-PH1{slash}OSC=>-Pad6)") (class "Default")
      (node (ref "U3") (pin "6") (pinfunction "PH1/OSC=>_6") (pintype "bidirectional"))
    )
    (net (code "80") (name "unconnected-(U4-SHDN-Pad5)") (class "Default")
      (node (ref "U4") (pin "5") (pinfunction "SHDN_5") (pintype "bidirectional"))
    )
    (net (code "81") (name "unconnected-(U5-SHDN-Pad5)") (class "Default")
      (node (ref "U5") (pin "5") (pinfunction "SHDN_5") (pintype "bidirectional"))
    )
    (net (code "82") (name "unconnected-(U11-A-Pad1)") (class "Default")
      (node (ref "U11") (pin "1") (pinfunction "A_1") (pintype "bidirectional"))
    )
    (net (code "83") (name "unconnected-(U12-A-Pad1)") (class "Default")
      (node (ref "U12") (pin "1") (pinfunction "A_1") (pintype "bidirectional"))
    )
    (net (code "84") (name "unconnected-(XTAL1-TRI-Pad1)") (class "Default")
      (node (ref "XTAL1") (pin "1") (pinfunction "TRI_1") (pintype "bidirectional"))
    )
  )
)
